# TM85.net
KiCad netlist of a schematic drawn in EAGLE
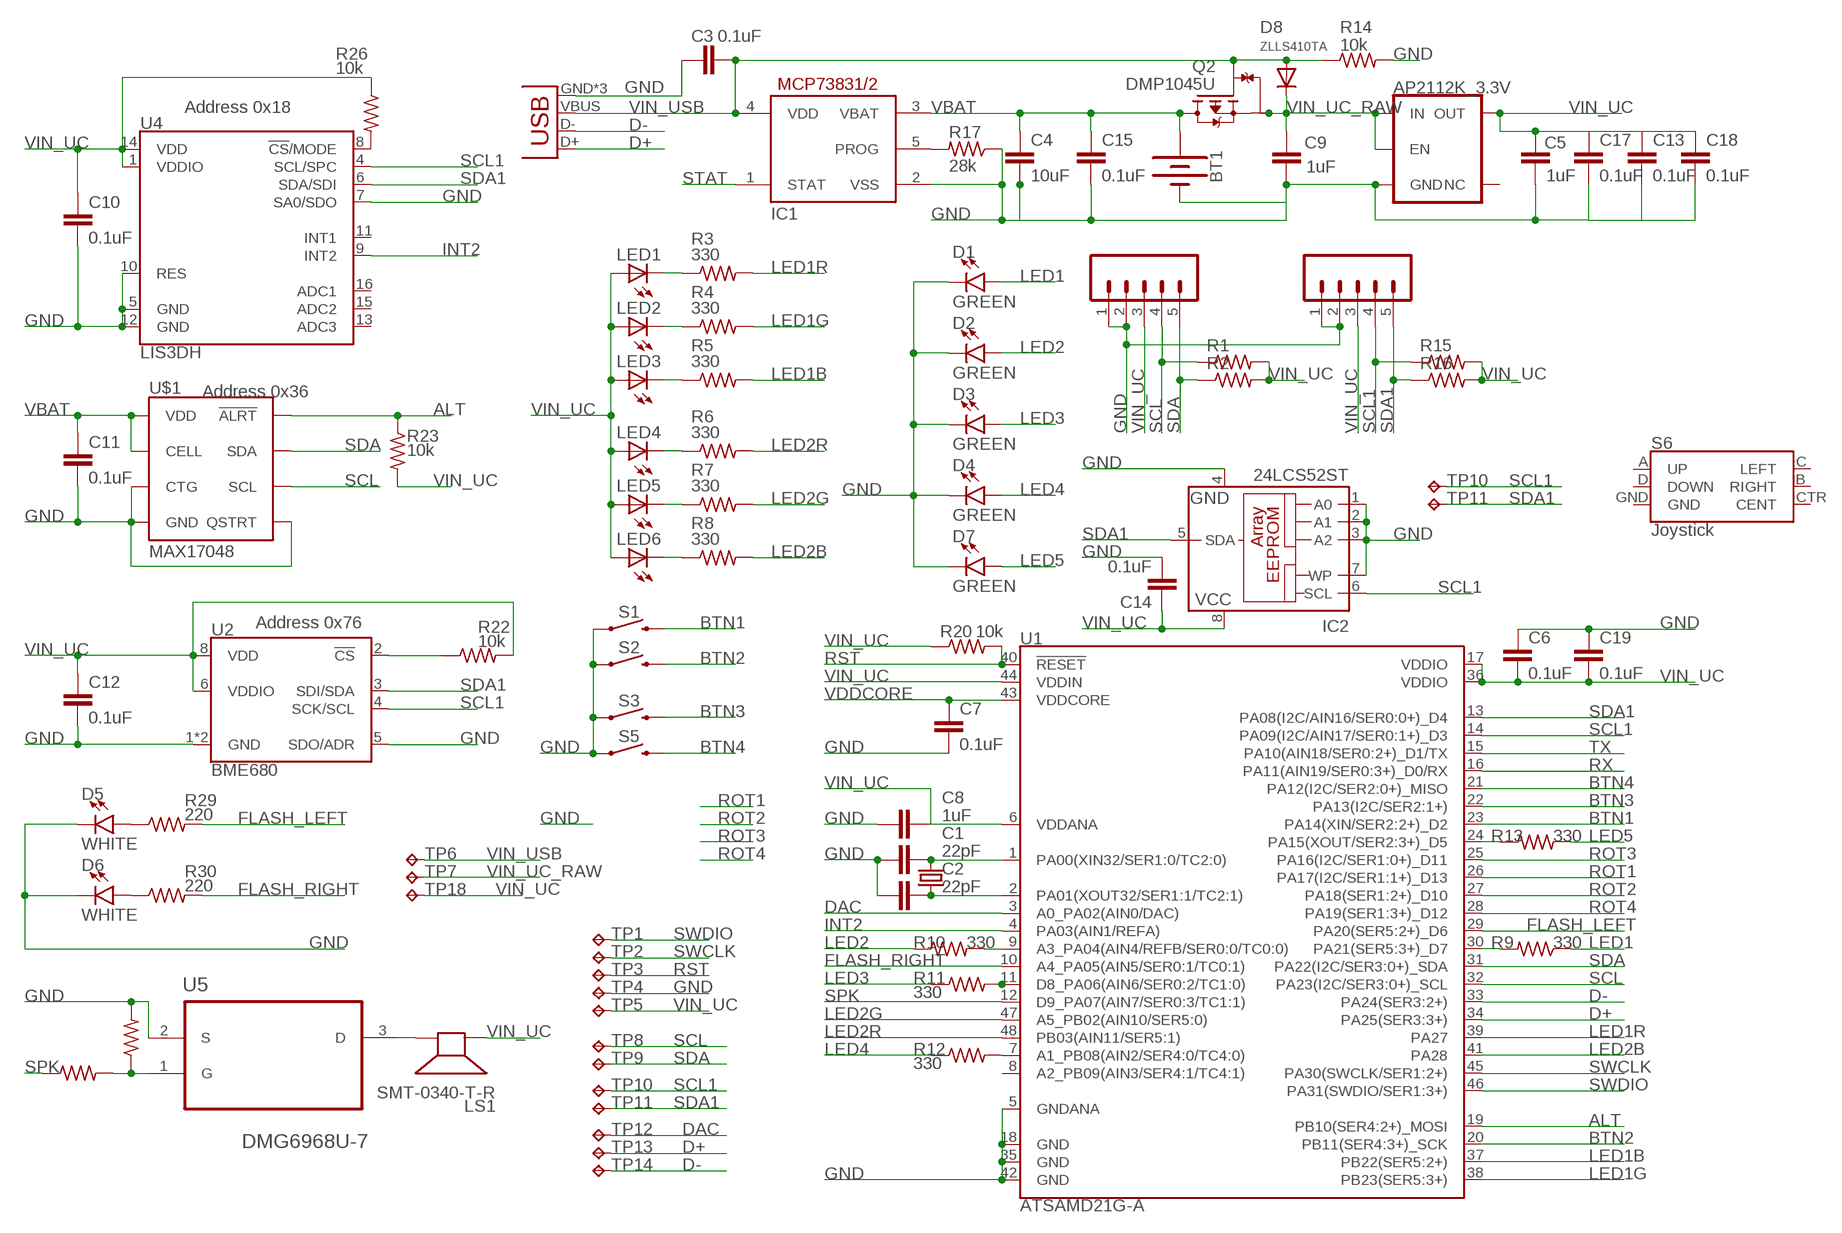
[diagram p0: schematic, sheet 1]

(export (version "E")
  (design (tool "Eeschema 10.0.6"))
  (components
    (comp (ref "AP2112K_3.3V")
      (value "3.3V")
      (footprint "eagle-import:SOT23-5")
      (libsource (lib "eagle-import") (part "V_REG_AP2112K-3.3V"))
    )
    (comp (ref "BT1")
      (value "BATTERY-20MM_SMD_4LEGS_OVERPASTE_INNER")
      (footprint "eagle-import:BATTCON_20MM_4LEGS_OVERPASTE_INNER")
      (libsource (lib "eagle-import") (part "BATTERY-20MM_SMD_4LEGS_OVERPASTE_INNER"))
    )
    (comp (ref "C1")
      (value "22pF")
      (footprint "eagle-import:C0402")
      (libsource (lib "eagle-import") (part "C-EUC0402"))
    )
    (comp (ref "C2")
      (value "22pF")
      (footprint "eagle-import:C0402")
      (libsource (lib "eagle-import") (part "C-EUC0402"))
    )
    (comp (ref "C3")
      (value "0.1uF")
      (footprint "eagle-import:C0402")
      (libsource (lib "eagle-import") (part "C-EUC0402"))
    )
    (comp (ref "C4")
      (value "10uF")
      (footprint "eagle-import:C0402")
      (libsource (lib "eagle-import") (part "C-EUC0402"))
    )
    (comp (ref "C5")
      (value "1uF")
      (footprint "eagle-import:C0402")
      (libsource (lib "eagle-import") (part "C-EUC0402"))
    )
    (comp (ref "C6")
      (value "0.1uF")
      (footprint "eagle-import:C0402")
      (libsource (lib "eagle-import") (part "C-EUC0402"))
    )
    (comp (ref "C7")
      (value "0.1uF")
      (footprint "eagle-import:C0402")
      (libsource (lib "eagle-import") (part "C-EUC0402"))
    )
    (comp (ref "C8")
      (value "1uF")
      (footprint "eagle-import:C0402")
      (libsource (lib "eagle-import") (part "C-EUC0402"))
    )
    (comp (ref "C9")
      (value "1uF")
      (footprint "eagle-import:C0402")
      (libsource (lib "eagle-import") (part "C-EUC0402"))
    )
    (comp (ref "C10")
      (value "0.1uF")
      (footprint "eagle-import:C0402")
      (libsource (lib "eagle-import") (part "C-EUC0402"))
    )
    (comp (ref "C11")
      (value "0.1uF")
      (footprint "eagle-import:C0402")
      (libsource (lib "eagle-import") (part "C-EUC0402"))
    )
    (comp (ref "C12")
      (value "0.1uF")
      (footprint "eagle-import:C0402")
      (libsource (lib "eagle-import") (part "C-EUC0402"))
    )
    (comp (ref "C13")
      (value "0.1uF")
      (footprint "eagle-import:C0402")
      (libsource (lib "eagle-import") (part "C-EUC0402"))
    )
    (comp (ref "C14")
      (value "0.1uF")
      (footprint "eagle-import:C0402")
      (libsource (lib "eagle-import") (part "C-EUC0402"))
    )
    (comp (ref "C15")
      (value "0.1uF")
      (footprint "eagle-import:C0402")
      (libsource (lib "eagle-import") (part "C-EUC0402"))
    )
    (comp (ref "C17")
      (value "0.1uF")
      (footprint "eagle-import:C0402")
      (libsource (lib "eagle-import") (part "C-EUC0402"))
    )
    (comp (ref "C18")
      (value "0.1uF")
      (footprint "eagle-import:C0402")
      (libsource (lib "eagle-import") (part "C-EUC0402"))
    )
    (comp (ref "C19")
      (value "0.1uF")
      (footprint "eagle-import:C0402")
      (libsource (lib "eagle-import") (part "C-EUC0402"))
    )
    (comp (ref "D1")
      (value "GREEN")
      (footprint "eagle-import:LED-1206")
      (libsource (lib "eagle-import") (part "LED-GREEN1206"))
    )
    (comp (ref "D2")
      (value "GREEN")
      (footprint "eagle-import:LED-1206")
      (libsource (lib "eagle-import") (part "LED-GREEN1206"))
    )
    (comp (ref "D3")
      (value "GREEN")
      (footprint "eagle-import:LED-1206")
      (libsource (lib "eagle-import") (part "LED-GREEN1206"))
    )
    (comp (ref "D4")
      (value "GREEN")
      (footprint "eagle-import:LED-1206")
      (libsource (lib "eagle-import") (part "LED-GREEN1206"))
    )
    (comp (ref "D5")
      (value "WHITE")
      (footprint "eagle-import:LED-1206")
      (libsource (lib "eagle-import") (part "LED-WHITE1206"))
    )
    (comp (ref "D6")
      (value "WHITE")
      (footprint "eagle-import:LED-1206")
      (libsource (lib "eagle-import") (part "LED-WHITE1206"))
    )
    (comp (ref "D7")
      (value "GREEN")
      (footprint "eagle-import:LED-1206")
      (libsource (lib "eagle-import") (part "LED-GREEN1206"))
    )
    (comp (ref "D8")
      (value "ZLLS410TA")
      (footprint "eagle-import:SOD-323F")
      (libsource (lib "eagle-import") (part "DIODESOD-323F"))
    )
    (comp (ref "IC1")
      (value "MCP73831/OT")
      (footprint "eagle-import:SOT23-5L")
      (libsource (lib "eagle-import") (part "MCP73831/OT"))
    )
    (comp (ref "IC2")
      (value "24LCS52ST")
      (footprint "eagle-import:TSSOP8")
      (fields (field (name "MF") "MICROCHIP") (field (name "MPN") "24LCS52T/ST"))
      (libsource (lib "eagle-import") (part "24STLCS52"))
    )
    (comp (ref "JP2")
      (value "USB-MICROB")
      (footprint "eagle-import:USB-MICROB")
      (libsource (lib "eagle-import") (part "USB-MICROB"))
    )
    (comp (ref "LCD1")
      (value "CONN_05VERT_FEMALE_HEADER")
      (footprint "eagle-import:1X05_SMD_VERTICAL_COMBO")
      (libsource (lib "eagle-import") (part "CONN_05VERT_FEMALE_HEADER"))
    )
    (comp (ref "LCD2")
      (value "CONN_05VERT_FEMALE_HEADER")
      (footprint "eagle-import:1X05_SMD_VERTICAL_COMBO")
      (libsource (lib "eagle-import") (part "CONN_05VERT_FEMALE_HEADER"))
    )
    (comp (ref "LED1")
      (value "LEDCHIPLED_0805")
      (footprint "eagle-import:CHIPLED_0805")
      (libsource (lib "eagle-import") (part "LEDCHIPLED_0805"))
    )
    (comp (ref "LED2")
      (value "LEDCHIPLED_0805")
      (footprint "eagle-import:CHIPLED_0805")
      (libsource (lib "eagle-import") (part "LEDCHIPLED_0805"))
    )
    (comp (ref "LED3")
      (value "LEDCHIPLED_0805")
      (footprint "eagle-import:CHIPLED_0805")
      (libsource (lib "eagle-import") (part "LEDCHIPLED_0805"))
    )
    (comp (ref "LED4")
      (value "LEDCHIPLED_0805")
      (footprint "eagle-import:CHIPLED_0805")
      (libsource (lib "eagle-import") (part "LEDCHIPLED_0805"))
    )
    (comp (ref "LED5")
      (value "LEDCHIPLED_0805")
      (footprint "eagle-import:CHIPLED_0805")
      (libsource (lib "eagle-import") (part "LEDCHIPLED_0805"))
    )
    (comp (ref "LED6")
      (value "LEDCHIPLED_0805")
      (footprint "eagle-import:CHIPLED_0805")
      (libsource (lib "eagle-import") (part "LEDCHIPLED_0805"))
    )
    (comp (ref "LS1")
      (value "SMT-0340-T-R")
      (footprint "eagle-import:XDCR_SMT-0340-T-R")
      (fields (field (name "MANUFACTURER") "Pui Audio"))
      (libsource (lib "eagle-import") (part "SMT-0340-T-R"))
    )
    (comp (ref "Q2")
      (value "DMP1045U")
      (footprint "eagle-import:SOT91P240X110-3N")
      (fields (field (name "MF") "Diodes Inc."))
      (libsource (lib "eagle-import") (part "DMP1045U"))
    )
    (comp (ref "R1")
      (value "R-US_R0402")
      (footprint "eagle-import:R0402")
      (libsource (lib "eagle-import") (part "adafruit_25768682_R-US_R0402"))
    )
    (comp (ref "R2")
      (value "R-US_R0402")
      (footprint "eagle-import:R0402")
      (libsource (lib "eagle-import") (part "adafruit_25768682_R-US_R0402"))
    )
    (comp (ref "R3")
      (value "330")
      (footprint "eagle-import:R0402")
      (libsource (lib "eagle-import") (part "rcl_334_R-US_R0402"))
    )
    (comp (ref "R4")
      (value "330")
      (footprint "eagle-import:R0402")
      (libsource (lib "eagle-import") (part "rcl_334_R-US_R0402"))
    )
    (comp (ref "R5")
      (value "330")
      (footprint "eagle-import:R0402")
      (libsource (lib "eagle-import") (part "rcl_334_R-US_R0402"))
    )
    (comp (ref "R6")
      (value "330")
      (footprint "eagle-import:R0402")
      (libsource (lib "eagle-import") (part "rcl_334_R-US_R0402"))
    )
    (comp (ref "R7")
      (value "330")
      (footprint "eagle-import:R0402")
      (libsource (lib "eagle-import") (part "rcl_334_R-US_R0402"))
    )
    (comp (ref "R8")
      (value "330")
      (footprint "eagle-import:R0402")
      (libsource (lib "eagle-import") (part "rcl_334_R-US_R0402"))
    )
    (comp (ref "R9")
      (value "330")
      (footprint "eagle-import:R0402")
      (libsource (lib "eagle-import") (part "rcl_334_R-US_R0402"))
    )
    (comp (ref "R10")
      (value "330")
      (footprint "eagle-import:R0402")
      (libsource (lib "eagle-import") (part "rcl_334_R-US_R0402"))
    )
    (comp (ref "R11")
      (value "330")
      (footprint "eagle-import:R0402")
      (libsource (lib "eagle-import") (part "rcl_334_R-US_R0402"))
    )
    (comp (ref "R12")
      (value "330")
      (footprint "eagle-import:R0402")
      (libsource (lib "eagle-import") (part "rcl_334_R-US_R0402"))
    )
    (comp (ref "R13")
      (value "330")
      (footprint "eagle-import:R0402")
      (libsource (lib "eagle-import") (part "rcl_334_R-US_R0402"))
    )
    (comp (ref "R14")
      (value "10k")
      (footprint "eagle-import:R0402")
      (libsource (lib "eagle-import") (part "R-US_R0402"))
    )
    (comp (ref "R15")
      (value "R-US_R0402")
      (footprint "eagle-import:R0402")
      (libsource (lib "eagle-import") (part "adafruit_25768682_R-US_R0402"))
    )
    (comp (ref "R16")
      (value "R-US_R0402")
      (footprint "eagle-import:R0402")
      (libsource (lib "eagle-import") (part "adafruit_25768682_R-US_R0402"))
    )
    (comp (ref "R17")
      (value "28k")
      (footprint "eagle-import:R0402")
      (libsource (lib "eagle-import") (part "adafruit_25768682_R-US_R0402"))
    )
    (comp (ref "R18")
      (value "220")
      (footprint "eagle-import:R0402")
      (libsource (lib "eagle-import") (part "rcl_334_R-US_R0402"))
    )
    (comp (ref "R19")
      (value "220")
      (footprint "eagle-import:R0402")
      (libsource (lib "eagle-import") (part "rcl_334_R-US_R0402"))
    )
    (comp (ref "R20")
      (value "10k")
      (footprint "eagle-import:R0402")
      (libsource (lib "eagle-import") (part "adafruit_25768682_R-US_R0402"))
    )
    (comp (ref "R22")
      (value "10k")
      (footprint "eagle-import:R0402")
      (libsource (lib "eagle-import") (part "rcl_334_R-US_R0402"))
    )
    (comp (ref "R23")
      (value "10k")
      (footprint "eagle-import:R0402")
      (libsource (lib "eagle-import") (part "rcl_334_R-US_R0402"))
    )
    (comp (ref "R26")
      (value "10k")
      (footprint "eagle-import:R0402")
      (libsource (lib "eagle-import") (part "rcl_334_R-US_R0402"))
    )
    (comp (ref "R29")
      (value "220")
      (footprint "eagle-import:R0402")
      (libsource (lib "eagle-import") (part "rcl_334_R-US_R0402"))
    )
    (comp (ref "R30")
      (value "220")
      (footprint "eagle-import:R0402")
      (libsource (lib "eagle-import") (part "rcl_334_R-US_R0402"))
    )
    (comp (ref "S1")
      (value "MOMENTARY-SWITCH-SPST-SMD-6.0X3.5MM")
      (footprint "eagle-import:TACTILE_SWITCH_SMD_6.0X3.5MM")
      (libsource (lib "eagle-import") (part "MOMENTARY-SWITCH-SPST-SMD-6.0X3.5MM"))
    )
    (comp (ref "S2")
      (value "MOMENTARY-SWITCH-SPST-SMD-6.0X3.5MM")
      (footprint "eagle-import:TACTILE_SWITCH_SMD_6.0X3.5MM")
      (libsource (lib "eagle-import") (part "MOMENTARY-SWITCH-SPST-SMD-6.0X3.5MM"))
    )
    (comp (ref "S3")
      (value "MOMENTARY-SWITCH-SPST-SMD-6.0X3.5MM")
      (footprint "eagle-import:TACTILE_SWITCH_SMD_6.0X3.5MM")
      (libsource (lib "eagle-import") (part "MOMENTARY-SWITCH-SPST-SMD-6.0X3.5MM"))
    )
    (comp (ref "S5")
      (value "MOMENTARY-SWITCH-SPST-SMD-6.0X3.5MM")
      (footprint "eagle-import:TACTILE_SWITCH_SMD_6.0X3.5MM")
      (libsource (lib "eagle-import") (part "MOMENTARY-SWITCH-SPST-SMD-6.0X3.5MM"))
    )
    (comp (ref "S6")
      (value "Joystick")
      (footprint "eagle-import:JOYSTICK_MINI")
      (libsource (lib "eagle-import") (part "JOYSTICK_MINI"))
    )
    (comp (ref "TP1")
      (value "TPTP14R")
      (footprint "eagle-import:TP14R")
      (libsource (lib "eagle-import") (part "TPTP14R"))
    )
    (comp (ref "TP2")
      (value "TPTP14R")
      (footprint "eagle-import:TP14R")
      (libsource (lib "eagle-import") (part "TPTP14R"))
    )
    (comp (ref "TP3")
      (value "TPTP14R")
      (footprint "eagle-import:TP14R")
      (libsource (lib "eagle-import") (part "TPTP14R"))
    )
    (comp (ref "TP4")
      (value "TPTP14R")
      (footprint "eagle-import:TP14R")
      (libsource (lib "eagle-import") (part "TPTP14R"))
    )
    (comp (ref "TP5")
      (value "TPTP14R")
      (footprint "eagle-import:TP14R")
      (libsource (lib "eagle-import") (part "TPTP14R"))
    )
    (comp (ref "TP6")
      (value "TPTP14R")
      (footprint "eagle-import:TP14R")
      (libsource (lib "eagle-import") (part "TPTP14R"))
    )
    (comp (ref "TP7")
      (value "TPTP14R")
      (footprint "eagle-import:TP14R")
      (libsource (lib "eagle-import") (part "TPTP14R"))
    )
    (comp (ref "TP8")
      (value "TPTP14R")
      (footprint "eagle-import:TP14R")
      (libsource (lib "eagle-import") (part "TPTP14R"))
    )
    (comp (ref "TP9")
      (value "TPTP14R")
      (footprint "eagle-import:TP14R")
      (libsource (lib "eagle-import") (part "TPTP14R"))
    )
    (comp (ref "TP10")
      (value "TPTP14R")
      (footprint "eagle-import:TP14R")
      (libsource (lib "eagle-import") (part "TPTP14R"))
    )
    (comp (ref "TP11")
      (value "TPTP14R")
      (footprint "eagle-import:TP14R")
      (libsource (lib "eagle-import") (part "TPTP14R"))
    )
    (comp (ref "TP12")
      (value "TPTP14R")
      (footprint "eagle-import:TP14R")
      (libsource (lib "eagle-import") (part "TPTP14R"))
    )
    (comp (ref "TP13")
      (value "TPTP14R")
      (footprint "eagle-import:TP14R")
      (libsource (lib "eagle-import") (part "TPTP14R"))
    )
    (comp (ref "TP14")
      (value "TPTP14R")
      (footprint "eagle-import:TP14R")
      (libsource (lib "eagle-import") (part "TPTP14R"))
    )
    (comp (ref "TP15")
      (value "TPTP14R")
      (footprint "eagle-import:TP14R")
      (libsource (lib "eagle-import") (part "TPTP14R"))
    )
    (comp (ref "TP16")
      (value "TPTP14R")
      (footprint "eagle-import:TP14R")
      (libsource (lib "eagle-import") (part "TPTP14R"))
    )
    (comp (ref "TP18")
      (value "TPTP14R")
      (footprint "eagle-import:TP14R")
      (libsource (lib "eagle-import") (part "TPTP14R"))
    )
    (comp (ref "U$1")
      (value "MAX17048")
      (footprint "eagle-import:DFN-8")
      (libsource (lib "eagle-import") (part "MAX17048DFN8"))
    )
    (comp (ref "U1")
      (value "ATSAMD21G-A")
      (footprint "eagle-import:TQFP-48")
      (libsource (lib "eagle-import") (part "ATSAMD21G-A"))
    )
    (comp (ref "U2")
      (value "BME680")
      (footprint "eagle-import:LGA3.0X3.0")
      (libsource (lib "eagle-import") (part "BME680-LGA"))
    )
    (comp (ref "U4")
      (value "LIS3DH")
      (footprint "eagle-import:LGA-16-3X3")
      (libsource (lib "eagle-import") (part "LIS3DH"))
    )
    (comp (ref "U5")
      (value "DMG6968U-7")
      (footprint "eagle-import:SOT95P240X110-3N")
      (fields (field (name "MF") "Diodes Inc."))
      (libsource (lib "eagle-import") (part "DMG6968U-7"))
    )
    (comp (ref "Y1")
      (value "32.768kHz")
      (footprint "eagle-import:CRYSTAL-SMD-3.2X1.5MM")
      (libsource (lib "eagle-import") (part "CRYSTAL-32.768KHZSMD-3.2X1.5"))
    )
  )
  (nets
    (net (code "1") (name "/ALT") (class "Default")
      (node (ref "R23") (pin "1") (pinfunction "1_1") (pintype "passive"))
      (node (ref "U$1") (pin "P$5") (pinfunction "~{ALRT}_P$5") (pintype "bidirectional"))
      (node (ref "U1") (pin "19") (pinfunction "PB10(SER4:2+)_MOSI_19") (pintype "bidirectional"))
    )
    (net (code "2") (name "/BTN1") (class "Default")
      (node (ref "S1") (pin "2") (pinfunction "2_2") (pintype "passive"))
      (node (ref "U1") (pin "23") (pinfunction "PA14(XIN/SER2:2+)_D2_23") (pintype "bidirectional"))
    )
    (net (code "3") (name "/BTN2") (class "Default")
      (node (ref "S2") (pin "2") (pinfunction "2_2") (pintype "passive"))
      (node (ref "U1") (pin "20") (pinfunction "PB11(SER4:3+)_SCK_20") (pintype "bidirectional"))
    )
    (net (code "4") (name "/BTN3") (class "Default")
      (node (ref "S3") (pin "2") (pinfunction "2_2") (pintype "passive"))
      (node (ref "U1") (pin "22") (pinfunction "PA13(I2C/SER2:1+)_22") (pintype "bidirectional"))
    )
    (net (code "5") (name "/BTN4") (class "Default")
      (node (ref "S5") (pin "2") (pinfunction "2_2") (pintype "passive"))
      (node (ref "U1") (pin "21") (pinfunction "PA12(I2C/SER2:0+)_MISO_21") (pintype "bidirectional"))
    )
    (net (code "6") (name "/D+") (class "Default")
      (node (ref "JP2") (pin "D+") (pinfunction "D+_D+") (pintype "bidirectional"))
      (node (ref "TP13") (pin "TP") (pinfunction "TP_TP") (pintype "input"))
      (node (ref "U1") (pin "34") (pinfunction "PA25(SER3:3+)_34") (pintype "bidirectional"))
    )
    (net (code "7") (name "/D-") (class "Default")
      (node (ref "JP2") (pin "D-") (pinfunction "D-_D-") (pintype "bidirectional"))
      (node (ref "TP14") (pin "TP") (pinfunction "TP_TP") (pintype "input"))
      (node (ref "U1") (pin "33") (pinfunction "PA24(SER3:2+)_33") (pintype "bidirectional"))
    )
    (net (code "8") (name "/DAC") (class "Default")
      (node (ref "TP12") (pin "TP") (pinfunction "TP_TP") (pintype "input"))
      (node (ref "U1") (pin "3") (pinfunction "A0_PA02(AIN0/DAC)_3") (pintype "bidirectional"))
    )
    (net (code "9") (name "/FLASH_LEFT") (class "Default")
      (node (ref "R29") (pin "2") (pinfunction "2_2") (pintype "passive"))
      (node (ref "U1") (pin "29") (pinfunction "PA20(SER5:2+)_D6_29") (pintype "bidirectional"))
    )
    (net (code "10") (name "/FLASH_RIGHT") (class "Default")
      (node (ref "R30") (pin "2") (pinfunction "2_2") (pintype "passive"))
      (node (ref "U1") (pin "10") (pinfunction "A4_PA05(AIN5/SER0:1/TC0:1)_10") (pintype "bidirectional"))
    )
    (net (code "11") (name "/GND") (class "Default")
      (node (ref "AP2112K_3.3V") (pin "2") (pinfunction "GND_2") (pintype "input"))
      (node (ref "BT1") (pin "2") (pinfunction "-_2") (pintype "power_in"))
      (node (ref "C1") (pin "1") (pinfunction "1_1") (pintype "passive"))
      (node (ref "C10") (pin "2") (pinfunction "2_2") (pintype "passive"))
      (node (ref "C11") (pin "2") (pinfunction "2_2") (pintype "passive"))
      (node (ref "C12") (pin "2") (pinfunction "2_2") (pintype "passive"))
      (node (ref "C13") (pin "2") (pinfunction "2_2") (pintype "passive"))
      (node (ref "C14") (pin "2") (pinfunction "2_2") (pintype "passive"))
      (node (ref "C15") (pin "2") (pinfunction "2_2") (pintype "passive"))
      (node (ref "C17") (pin "2") (pinfunction "2_2") (pintype "passive"))
      (node (ref "C18") (pin "2") (pinfunction "2_2") (pintype "passive"))
      (node (ref "C19") (pin "1") (pinfunction "1_1") (pintype "passive"))
      (node (ref "C2") (pin "1") (pinfunction "1_1") (pintype "passive"))
      (node (ref "C3") (pin "1") (pinfunction "1_1") (pintype "passive"))
      (node (ref "C4") (pin "2") (pinfunction "2_2") (pintype "passive"))
      (node (ref "C5") (pin "2") (pinfunction "2_2") (pintype "passive"))
      (node (ref "C6") (pin "1") (pinfunction "1_1") (pintype "passive"))
      (node (ref "C7") (pin "2") (pinfunction "2_2") (pintype "passive"))
      (node (ref "C8") (pin "1") (pinfunction "1_1") (pintype "passive"))
      (node (ref "C9") (pin "2") (pinfunction "2_2") (pintype "passive"))
      (node (ref "D1") (pin "C") (pinfunction "C_C") (pintype "passive"))
      (node (ref "D2") (pin "C") (pinfunction "C_C") (pintype "passive"))
      (node (ref "D3") (pin "C") (pinfunction "C_C") (pintype "passive"))
      (node (ref "D4") (pin "C") (pinfunction "C_C") (pintype "passive"))
      (node (ref "D5") (pin "C") (pinfunction "C_C") (pintype "passive"))
      (node (ref "D6") (pin "C") (pinfunction "C_C") (pintype "passive"))
      (node (ref "D7") (pin "C") (pinfunction "C_C") (pintype "passive"))
      (node (ref "IC1") (pin "2") (pinfunction "VSS_2") (pintype "power_in"))
      (node (ref "IC2") (pin "1") (pinfunction "A0_1") (pintype "input"))
      (node (ref "IC2") (pin "2") (pinfunction "A1_2") (pintype "input"))
      (node (ref "IC2") (pin "3") (pinfunction "A2_3") (pintype "input"))
      (node (ref "IC2") (pin "4") (pinfunction "GND_4") (pintype "power_in"))
      (node (ref "IC2") (pin "7") (pinfunction "WP_7") (pintype "input"))
      (node (ref "JP2") (pin "GND") (pinfunction "GND_GND") (pintype "bidirectional"))
      (node (ref "JP2") (pin "MT1") (pinfunction "GND_MT1") (pintype "bidirectional"))
      (node (ref "JP2") (pin "MT2") (pinfunction "GND_MT2") (pintype "bidirectional"))
      (node (ref "LCD1") (pin "1") (pinfunction "1_1") (pintype "passive"))
      (node (ref "LCD1") (pin "2") (pinfunction "2_2") (pintype "passive"))
      (node (ref "LCD2") (pin "1") (pinfunction "1_1") (pintype "passive"))
      (node (ref "LCD2") (pin "2") (pinfunction "2_2") (pintype "passive"))
      (node (ref "R14") (pin "2") (pinfunction "2_2") (pintype "passive"))
      (node (ref "R17") (pin "1") (pinfunction "1_1") (pintype "passive"))
      (node (ref "R19") (pin "2") (pinfunction "2_2") (pintype "passive"))
      (node (ref "S1") (pin "1") (pinfunction "1_1") (pintype "passive"))
      (node (ref "S2") (pin "1") (pinfunction "1_1") (pintype "passive"))
      (node (ref "S3") (pin "1") (pinfunction "1_1") (pintype "passive"))
      (node (ref "S5") (pin "1") (pinfunction "1_1") (pintype "passive"))
      (node (ref "TP4") (pin "TP") (pinfunction "TP_TP") (pintype "input"))
      (node (ref "U$1") (pin "P$1") (pinfunction "CTG_P$1") (pintype "input"))
      (node (ref "U$1") (pin "P$4") (pinfunction "GND_P$4") (pintype "bidirectional"))
      (node (ref "U$1") (pin "P$6") (pinfunction "QSTRT_P$6") (pintype "bidirectional"))
      (node (ref "U$1") (pin "P$9") (pinfunction "GND_P$9") (pintype "bidirectional"))
      (node (ref "U1") (pin "18") (pinfunction "GND_18") (pintype "bidirectional"))
      (node (ref "U1") (pin "35") (pinfunction "GND_35") (pintype "bidirectional"))
      (node (ref "U1") (pin "42") (pinfunction "GND_42") (pintype "bidirectional"))
      (node (ref "U1") (pin "5") (pinfunction "GNDANA_5") (pintype "bidirectional"))
      (node (ref "U2") (pin "1") (pinfunction "GND_1") (pintype "bidirectional"))
      (node (ref "U2") (pin "5") (pinfunction "SDO/ADR_5") (pintype "bidirectional"))
      (node (ref "U2") (pin "7") (pinfunction "GND_7") (pintype "bidirectional"))
      (node (ref "U4") (pin "10") (pinfunction "RES_10") (pintype "bidirectional"))
      (node (ref "U4") (pin "12") (pinfunction "GND_12") (pintype "bidirectional"))
      (node (ref "U4") (pin "5") (pinfunction "GND_5") (pintype "bidirectional"))
      (node (ref "U4") (pin "7") (pinfunction "SA0/SDO_7") (pintype "bidirectional"))
      (node (ref "U5") (pin "2") (pinfunction "S_2") (pintype "passive"))
    )
    (net (code "12") (name "/INT2") (class "Default")
      (node (ref "U1") (pin "4") (pinfunction "PA03(AIN1/REFA)_4") (pintype "bidirectional"))
      (node (ref "U4") (pin "9") (pinfunction "INT2_9") (pintype "bidirectional"))
    )
    (net (code "13") (name "/LED1") (class "Default")
      (node (ref "D1") (pin "A") (pinfunction "A_A") (pintype "passive"))
      (node (ref "R9") (pin "1") (pinfunction "1_1") (pintype "passive"))
    )
    (net (code "14") (name "/LED1B") (class "Default")
      (node (ref "R5") (pin "2") (pinfunction "2_2") (pintype "passive"))
      (node (ref "U1") (pin "37") (pinfunction "PB22(SER5:2+)_37") (pintype "bidirectional"))
    )
    (net (code "15") (name "/LED1G") (class "Default")
      (node (ref "R4") (pin "2") (pinfunction "2_2") (pintype "passive"))
      (node (ref "U1") (pin "38") (pinfunction "PB23(SER5:3+)_38") (pintype "bidirectional"))
    )
    (net (code "16") (name "/LED1R") (class "Default")
      (node (ref "R3") (pin "2") (pinfunction "2_2") (pintype "passive"))
      (node (ref "U1") (pin "39") (pinfunction "PA27_39") (pintype "bidirectional"))
    )
    (net (code "17") (name "/LED2") (class "Default")
      (node (ref "D2") (pin "A") (pinfunction "A_A") (pintype "passive"))
      (node (ref "R10") (pin "1") (pinfunction "1_1") (pintype "passive"))
    )
    (net (code "18") (name "/LED2B") (class "Default")
      (node (ref "R8") (pin "2") (pinfunction "2_2") (pintype "passive"))
      (node (ref "U1") (pin "41") (pinfunction "PA28_41") (pintype "bidirectional"))
    )
    (net (code "19") (name "/LED2G") (class "Default")
      (node (ref "R7") (pin "2") (pinfunction "2_2") (pintype "passive"))
      (node (ref "U1") (pin "47") (pinfunction "A5_PB02(AIN10/SER5:0)_47") (pintype "bidirectional"))
    )
    (net (code "20") (name "/LED2R") (class "Default")
      (node (ref "R6") (pin "2") (pinfunction "2_2") (pintype "passive"))
      (node (ref "U1") (pin "48") (pinfunction "PB03(AIN11/SER5:1)_48") (pintype "bidirectional"))
    )
    (net (code "21") (name "/LED3") (class "Default")
      (node (ref "D3") (pin "A") (pinfunction "A_A") (pintype "passive"))
      (node (ref "R11") (pin "1") (pinfunction "1_1") (pintype "passive"))
    )
    (net (code "22") (name "/LED4") (class "Default")
      (node (ref "D4") (pin "A") (pinfunction "A_A") (pintype "passive"))
      (node (ref "R12") (pin "1") (pinfunction "1_1") (pintype "passive"))
    )
    (net (code "23") (name "/LED5") (class "Default")
      (node (ref "D7") (pin "A") (pinfunction "A_A") (pintype "passive"))
      (node (ref "R13") (pin "2") (pinfunction "2_2") (pintype "passive"))
    )
    (net (code "24") (name "/ROT1") (class "Default")
      (node (ref "U1") (pin "26") (pinfunction "PA17(I2C/SER1:1+)_D13_26") (pintype "bidirectional"))
    )
    (net (code "25") (name "/ROT2") (class "Default")
      (node (ref "U1") (pin "27") (pinfunction "PA18(SER1:2+)_D10_27") (pintype "bidirectional"))
    )
    (net (code "26") (name "/ROT3") (class "Default")
      (node (ref "U1") (pin "25") (pinfunction "PA16(I2C/SER1:0+)_D11_25") (pintype "bidirectional"))
    )
    (net (code "27") (name "/ROT4") (class "Default")
      (node (ref "U1") (pin "28") (pinfunction "PA19(SER1:3+)_D12_28") (pintype "bidirectional"))
    )
    (net (code "28") (name "/RST") (class "Default")
      (node (ref "R20") (pin "2") (pinfunction "2_2") (pintype "passive"))
      (node (ref "TP3") (pin "TP") (pinfunction "TP_TP") (pintype "input"))
      (node (ref "U1") (pin "40") (pinfunction "~{RESET}_40") (pintype "bidirectional"))
    )
    (net (code "29") (name "/RX") (class "Default")
      (node (ref "U1") (pin "16") (pinfunction "PA11(AIN19/SER0:3+)_D0/RX_16") (pintype "bidirectional"))
    )
    (net (code "30") (name "/SCL") (class "Default")
      (node (ref "LCD1") (pin "4") (pinfunction "4_4") (pintype "passive"))
      (node (ref "R1") (pin "1") (pinfunction "1_1") (pintype "passive"))
      (node (ref "TP8") (pin "TP") (pinfunction "TP_TP") (pintype "input"))
      (node (ref "U$1") (pin "P$7") (pinfunction "SCL_P$7") (pintype "output"))
      (node (ref "U1") (pin "32") (pinfunction "PA23(I2C/SER3:0+)_SCL_32") (pintype "bidirectional"))
    )
    (net (code "31") (name "/SCL1") (class "Default")
      (node (ref "IC2") (pin "6") (pinfunction "SCL_6") (pintype "input"))
      (node (ref "LCD2") (pin "4") (pinfunction "4_4") (pintype "passive"))
      (node (ref "R15") (pin "1") (pinfunction "1_1") (pintype "passive"))
      (node (ref "TP10") (pin "TP") (pinfunction "TP_TP") (pintype "input"))
      (node (ref "TP15") (pin "TP") (pinfunction "TP_TP") (pintype "input"))
      (node (ref "U1") (pin "14") (pinfunction "PA09(I2C/AIN17/SER0:1+)_D3_14") (pintype "bidirectional"))
      (node (ref "U2") (pin "4") (pinfunction "SCK/SCL_4") (pintype "bidirectional"))
      (node (ref "U4") (pin "4") (pinfunction "SCL/SPC_4") (pintype "bidirectional"))
    )
    (net (code "32") (name "/SDA") (class "Default")
      (node (ref "LCD1") (pin "5") (pinfunction "5_5") (pintype "passive"))
      (node (ref "R2") (pin "1") (pinfunction "1_1") (pintype "passive"))
      (node (ref "TP9") (pin "TP") (pinfunction "TP_TP") (pintype "input"))
      (node (ref "U$1") (pin "P$8") (pinfunction "SDA_P$8") (pintype "input"))
      (node (ref "U1") (pin "31") (pinfunction "PA22(I2C/SER3:0+)_SDA_31") (pintype "bidirectional"))
    )
    (net (code "33") (name "/SDA1") (class "Default")
      (node (ref "IC2") (pin "5") (pinfunction "SDA_5") (pintype "bidirectional"))
      (node (ref "LCD2") (pin "5") (pinfunction "5_5") (pintype "passive"))
      (node (ref "R16") (pin "1") (pinfunction "1_1") (pintype "passive"))
      (node (ref "TP11") (pin "TP") (pinfunction "TP_TP") (pintype "input"))
      (node (ref "TP16") (pin "TP") (pinfunction "TP_TP") (pintype "input"))
      (node (ref "U1") (pin "13") (pinfunction "PA08(I2C/AIN16/SER0:0+)_D4_13") (pintype "bidirectional"))
      (node (ref "U2") (pin "3") (pinfunction "SDI/SDA_3") (pintype "bidirectional"))
      (node (ref "U4") (pin "6") (pinfunction "SDA/SDI_6") (pintype "bidirectional"))
    )
    (net (code "34") (name "/SPK") (class "Default")
      (node (ref "R18") (pin "1") (pinfunction "1_1") (pintype "passive"))
      (node (ref "U1") (pin "12") (pinfunction "D9_PA07(AIN7/SER0:3/TC1:1)_12") (pintype "bidirectional"))
    )
    (net (code "35") (name "/STAT") (class "Default")
      (node (ref "IC1") (pin "1") (pinfunction "STAT_1") (pintype "output"))
    )
    (net (code "36") (name "/SWCLK") (class "Default")
      (node (ref "TP2") (pin "TP") (pinfunction "TP_TP") (pintype "input"))
      (node (ref "U1") (pin "45") (pinfunction "PA30(SWCLK/SER1:2+)_45") (pintype "bidirectional"))
    )
    (net (code "37") (name "/SWDIO") (class "Default")
      (node (ref "TP1") (pin "TP") (pinfunction "TP_TP") (pintype "input"))
      (node (ref "U1") (pin "46") (pinfunction "PA31(SWDIO/SER1:3+)_46") (pintype "bidirectional"))
    )
    (net (code "38") (name "/TX") (class "Default")
      (node (ref "U1") (pin "15") (pinfunction "PA10(AIN18/SER0:2+)_D1/TX_15") (pintype "bidirectional"))
    )
    (net (code "39") (name "/VBAT") (class "Default")
      (node (ref "BT1") (pin "1") (pinfunction "+_1") (pintype "power_in"))
      (node (ref "C11") (pin "1") (pinfunction "1_1") (pintype "passive"))
      (node (ref "C15") (pin "1") (pinfunction "1_1") (pintype "passive"))
      (node (ref "C4") (pin "1") (pinfunction "1_1") (pintype "passive"))
      (node (ref "IC1") (pin "3") (pinfunction "VBAT_3") (pintype "bidirectional"))
      (node (ref "Q2") (pin "3") (pinfunction "D_3") (pintype "passive"))
      (node (ref "U$1") (pin "P$2") (pinfunction "CELL_P$2") (pintype "input"))
      (node (ref "U$1") (pin "P$3") (pinfunction "VDD_P$3") (pintype "bidirectional"))
    )
    (net (code "40") (name "/VDDCORE") (class "Default")
      (node (ref "C7") (pin "1") (pinfunction "1_1") (pintype "passive"))
      (node (ref "U1") (pin "43") (pinfunction "VDDCORE_43") (pintype "bidirectional"))
    )
    (net (code "41") (name "/VIN_UC") (class "Default")
      (node (ref "AP2112K_3.3V") (pin "5") (pinfunction "OUT_5") (pintype "passive"))
      (node (ref "C10") (pin "1") (pinfunction "1_1") (pintype "passive"))
      (node (ref "C12") (pin "1") (pinfunction "1_1") (pintype "passive"))
      (node (ref "C13") (pin "1") (pinfunction "1_1") (pintype "passive"))
      (node (ref "C14") (pin "1") (pinfunction "1_1") (pintype "passive"))
      (node (ref "C17") (pin "1") (pinfunction "1_1") (pintype "passive"))
      (node (ref "C18") (pin "1") (pinfunction "1_1") (pintype "passive"))
      (node (ref "C19") (pin "2") (pinfunction "2_2") (pintype "passive"))
      (node (ref "C5") (pin "1") (pinfunction "1_1") (pintype "passive"))
      (node (ref "C6") (pin "2") (pinfunction "2_2") (pintype "passive"))
      (node (ref "C8") (pin "2") (pinfunction "2_2") (pintype "passive"))
      (node (ref "IC2") (pin "8") (pinfunction "VCC_8") (pintype "power_in"))
      (node (ref "LCD1") (pin "3") (pinfunction "3_3") (pintype "passive"))
      (node (ref "LCD2") (pin "3") (pinfunction "3_3") (pintype "passive"))
      (node (ref "LED1") (pin "A") (pinfunction "A_A") (pintype "passive"))
      (node (ref "LED2") (pin "A") (pinfunction "A_A") (pintype "passive"))
      (node (ref "LED3") (pin "A") (pinfunction "A_A") (pintype "passive"))
      (node (ref "LED4") (pin "A") (pinfunction "A_A") (pintype "passive"))
      (node (ref "LED5") (pin "A") (pinfunction "A_A") (pintype "passive"))
      (node (ref "LED6") (pin "A") (pinfunction "A_A") (pintype "passive"))
      (node (ref "LS1") (pin "P") (pinfunction "P_P") (pintype "passive"))
      (node (ref "R1") (pin "2") (pinfunction "2_2") (pintype "passive"))
      (node (ref "R15") (pin "2") (pinfunction "2_2") (pintype "passive"))
      (node (ref "R16") (pin "2") (pinfunction "2_2") (pintype "passive"))
      (node (ref "R2") (pin "2") (pinfunction "2_2") (pintype "passive"))
      (node (ref "R20") (pin "1") (pinfunction "1_1") (pintype "passive"))
      (node (ref "R22") (pin "2") (pinfunction "2_2") (pintype "passive"))
      (node (ref "R23") (pin "2") (pinfunction "2_2") (pintype "passive"))
      (node (ref "R26") (pin "1") (pinfunction "1_1") (pintype "passive"))
      (node (ref "TP18") (pin "TP") (pinfunction "TP_TP") (pintype "input"))
      (node (ref "TP5") (pin "TP") (pinfunction "TP_TP") (pintype "input"))
      (node (ref "U1") (pin "17") (pinfunction "VDDIO_17") (pintype "bidirectional"))
      (node (ref "U1") (pin "36") (pinfunction "VDDIO_36") (pintype "bidirectional"))
      (node (ref "U1") (pin "44") (pinfunction "VDDIN_44") (pintype "bidirectional"))
      (node (ref "U1") (pin "6") (pinfunction "VDDANA_6") (pintype "bidirectional"))
      (node (ref "U2") (pin "6") (pinfunction "VDDIO_6") (pintype "bidirectional"))
      (node (ref "U2") (pin "8") (pinfunction "VDD_8") (pintype "bidirectional"))
      (node (ref "U4") (pin "1") (pinfunction "VDDIO_1") (pintype "bidirectional"))
      (node (ref "U4") (pin "14") (pinfunction "VDD_14") (pintype "bidirectional"))
    )
    (net (code "42") (name "/VIN_UC_RAW") (class "Default")
      (node (ref "AP2112K_3.3V") (pin "1") (pinfunction "IN_1") (pintype "input"))
      (node (ref "AP2112K_3.3V") (pin "3") (pinfunction "EN_3") (pintype "input"))
      (node (ref "C9") (pin "1") (pinfunction "1_1") (pintype "passive"))
      (node (ref "D8") (pin "C") (pinfunction "C_C") (pintype "passive"))
      (node (ref "Q2") (pin "2") (pinfunction "S_2") (pintype "passive"))
      (node (ref "TP7") (pin "TP") (pinfunction "TP_TP") (pintype "input"))
    )
    (net (code "43") (name "/VIN_USB") (class "Default")
      (node (ref "C3") (pin "2") (pinfunction "2_2") (pintype "passive"))
      (node (ref "D8") (pin "A") (pinfunction "A_A") (pintype "passive"))
      (node (ref "IC1") (pin "4") (pinfunction "VDD_4") (pintype "power_in"))
      (node (ref "JP2") (pin "VBUS") (pinfunction "VBUS_VBUS") (pintype "bidirectional"))
      (node (ref "Q2") (pin "1") (pinfunction "G_1") (pintype "passive"))
      (node (ref "R14") (pin "1") (pinfunction "1_1") (pintype "passive"))
      (node (ref "TP6") (pin "TP") (pinfunction "TP_TP") (pintype "input"))
    )
    (net (code "44") (name "Net-(D5-PadA)") (class "Default")
      (node (ref "D5") (pin "A") (pinfunction "A_A") (pintype "passive"))
      (node (ref "R29") (pin "1") (pinfunction "1_1") (pintype "passive"))
    )
    (net (code "45") (name "Net-(D6-PadA)") (class "Default")
      (node (ref "D6") (pin "A") (pinfunction "A_A") (pintype "passive"))
      (node (ref "R30") (pin "1") (pinfunction "1_1") (pintype "passive"))
    )
    (net (code "46") (name "Net-(IC1-PROG)") (class "Default")
      (node (ref "IC1") (pin "5") (pinfunction "PROG_5") (pintype "input"))
      (node (ref "R17") (pin "2") (pinfunction "2_2") (pintype "passive"))
    )
    (net (code "47") (name "Net-(LED1-PadC)") (class "Default")
      (node (ref "LED1") (pin "C") (pinfunction "C_C") (pintype "passive"))
      (node (ref "R3") (pin "1") (pinfunction "1_1") (pintype "passive"))
    )
    (net (code "48") (name "Net-(LED2-PadC)") (class "Default")
      (node (ref "LED2") (pin "C") (pinfunction "C_C") (pintype "passive"))
      (node (ref "R4") (pin "1") (pinfunction "1_1") (pintype "passive"))
    )
    (net (code "49") (name "Net-(LED3-PadC)") (class "Default")
      (node (ref "LED3") (pin "C") (pinfunction "C_C") (pintype "passive"))
      (node (ref "R5") (pin "1") (pinfunction "1_1") (pintype "passive"))
    )
    (net (code "50") (name "Net-(LED4-PadC)") (class "Default")
      (node (ref "LED4") (pin "C") (pinfunction "C_C") (pintype "passive"))
      (node (ref "R6") (pin "1") (pinfunction "1_1") (pintype "passive"))
    )
    (net (code "51") (name "Net-(LED5-PadC)") (class "Default")
      (node (ref "LED5") (pin "C") (pinfunction "C_C") (pintype "passive"))
      (node (ref "R7") (pin "1") (pinfunction "1_1") (pintype "passive"))
    )
    (net (code "52") (name "Net-(LED6-PadC)") (class "Default")
      (node (ref "LED6") (pin "C") (pinfunction "C_C") (pintype "passive"))
      (node (ref "R8") (pin "1") (pinfunction "1_1") (pintype "passive"))
    )
    (net (code "53") (name "Net-(U1-A1_PB08(AIN2{slash}SER4:0{slash}TC4:0))") (class "Default")
      (node (ref "R12") (pin "2") (pinfunction "2_2") (pintype "passive"))
      (node (ref "U1") (pin "7") (pinfunction "A1_PB08(AIN2/SER4:0/TC4:0)_7") (pintype "bidirectional"))
    )
    (net (code "54") (name "Net-(U1-A3_PA04(AIN4{slash}REFB{slash}SER0:0{slash}TC0:0))") (class "Default")
      (node (ref "R10") (pin "2") (pinfunction "2_2") (pintype "passive"))
      (node (ref "U1") (pin "9") (pinfunction "A3_PA04(AIN4/REFB/SER0:0/TC0:0)_9") (pintype "bidirectional"))
    )
    (net (code "55") (name "Net-(U1-D8_PA06(AIN6{slash}SER0:2{slash}TC1:0))") (class "Default")
      (node (ref "R11") (pin "2") (pinfunction "2_2") (pintype "passive"))
      (node (ref "U1") (pin "11") (pinfunction "D8_PA06(AIN6/SER0:2/TC1:0)_11") (pintype "bidirectional"))
    )
    (net (code "56") (name "Net-(U1-PA00(XIN32{slash}SER1:0{slash}TC2:0))") (class "Default")
      (node (ref "C1") (pin "2") (pinfunction "2_2") (pintype "passive"))
      (node (ref "U1") (pin "1") (pinfunction "PA00(XIN32/SER1:0/TC2:0)_1") (pintype "bidirectional"))
      (node (ref "Y1") (pin "P$2") (pinfunction "2_P$2") (pintype "passive"))
    )
    (net (code "57") (name "Net-(U1-PA01(XOUT32{slash}SER1:1{slash}TC2:1))") (class "Default")
      (node (ref "C2") (pin "2") (pinfunction "2_2") (pintype "passive"))
      (node (ref "U1") (pin "2") (pinfunction "PA01(XOUT32/SER1:1/TC2:1)_2") (pintype "bidirectional"))
      (node (ref "Y1") (pin "P$1") (pinfunction "1_P$1") (pintype "passive"))
    )
    (net (code "58") (name "Net-(U1-PA15(XOUT{slash}SER2:3+)_D5)") (class "Default")
      (node (ref "R13") (pin "1") (pinfunction "1_1") (pintype "passive"))
      (node (ref "U1") (pin "24") (pinfunction "PA15(XOUT/SER2:3+)_D5_24") (pintype "bidirectional"))
    )
    (net (code "59") (name "Net-(U1-PA21(SER5:3+)_D7)") (class "Default")
      (node (ref "R9") (pin "2") (pinfunction "2_2") (pintype "passive"))
      (node (ref "U1") (pin "30") (pinfunction "PA21(SER5:3+)_D7_30") (pintype "bidirectional"))
    )
    (net (code "60") (name "Net-(U2-~{CS})") (class "Default")
      (node (ref "R22") (pin "1") (pinfunction "1_1") (pintype "passive"))
      (node (ref "U2") (pin "2") (pinfunction "~{CS}_2") (pintype "bidirectional"))
    )
    (net (code "61") (name "Net-(U4-~{CS}{slash}MODE)") (class "Default")
      (node (ref "R26") (pin "2") (pinfunction "2_2") (pintype "passive"))
      (node (ref "U4") (pin "8") (pinfunction "~{CS}/MODE_8") (pintype "bidirectional"))
    )
    (net (code "62") (name "Net-(U5-D)") (class "Default")
      (node (ref "LS1") (pin "N") (pinfunction "N_N") (pintype "passive"))
      (node (ref "U5") (pin "3") (pinfunction "D_3") (pintype "output"))
    )
    (net (code "63") (name "Net-(U5-G)") (class "Default")
      (node (ref "R18") (pin "2") (pinfunction "2_2") (pintype "passive"))
      (node (ref "R19") (pin "1") (pinfunction "1_1") (pintype "passive"))
      (node (ref "U5") (pin "1") (pinfunction "G_1") (pintype "power_in"))
    )
    (net (code "64") (name "unconnected-(AP2112K_3.3V-NC-Pad4)") (class "Default")
      (node (ref "AP2112K_3.3V") (pin "4") (pinfunction "NC_4") (pintype "no_connect"))
    )
    (net (code "65") (name "unconnected-(S6-CENT-PadCTR)") (class "Default")
      (node (ref "S6") (pin "CTR") (pinfunction "CENT_CTR") (pintype "bidirectional"))
    )
    (net (code "66") (name "unconnected-(S6-DOWN-PadD)") (class "Default")
      (node (ref "S6") (pin "D") (pinfunction "DOWN_D") (pintype "bidirectional"))
    )
    (net (code "67") (name "unconnected-(S6-LEFT-PadC)") (class "Default")
      (node (ref "S6") (pin "C") (pinfunction "LEFT_C") (pintype "bidirectional"))
    )
    (net (code "68") (name "unconnected-(S6-PadGND)") (class "Default")
      (node (ref "S6") (pin "GND") (pinfunction "GND_GND") (pintype "bidirectional"))
    )
    (net (code "69") (name "unconnected-(S6-RIGHT-PadB)") (class "Default")
      (node (ref "S6") (pin "B") (pinfunction "RIGHT_B") (pintype "bidirectional"))
    )
    (net (code "70") (name "unconnected-(S6-UP-PadA)") (class "Default")
      (node (ref "S6") (pin "A") (pinfunction "UP_A") (pintype "bidirectional"))
    )
    (net (code "71") (name "unconnected-(U1-A2_PB09(AIN3{slash}SER4:1{slash}TC4:1)-Pad8)") (class "Default")
      (node (ref "U1") (pin "8") (pinfunction "A2_PB09(AIN3/SER4:1/TC4:1)_8") (pintype "bidirectional"))
    )
    (net (code "72") (name "unconnected-(U4-ADC1-Pad16)") (class "Default")
      (node (ref "U4") (pin "16") (pinfunction "ADC1_16") (pintype "bidirectional"))
    )
    (net (code "73") (name "unconnected-(U4-ADC2-Pad15)") (class "Default")
      (node (ref "U4") (pin "15") (pinfunction "ADC2_15") (pintype "bidirectional"))
    )
    (net (code "74") (name "unconnected-(U4-ADC3-Pad13)") (class "Default")
      (node (ref "U4") (pin "13") (pinfunction "ADC3_13") (pintype "bidirectional"))
    )
    (net (code "75") (name "unconnected-(U4-INT1-Pad11)") (class "Default")
      (node (ref "U4") (pin "11") (pinfunction "INT1_11") (pintype "bidirectional"))
    )
  )
)
